# PROCESSOR_MEMORIES.net
KiCad netlist of a schematic drawn in Altium Designer
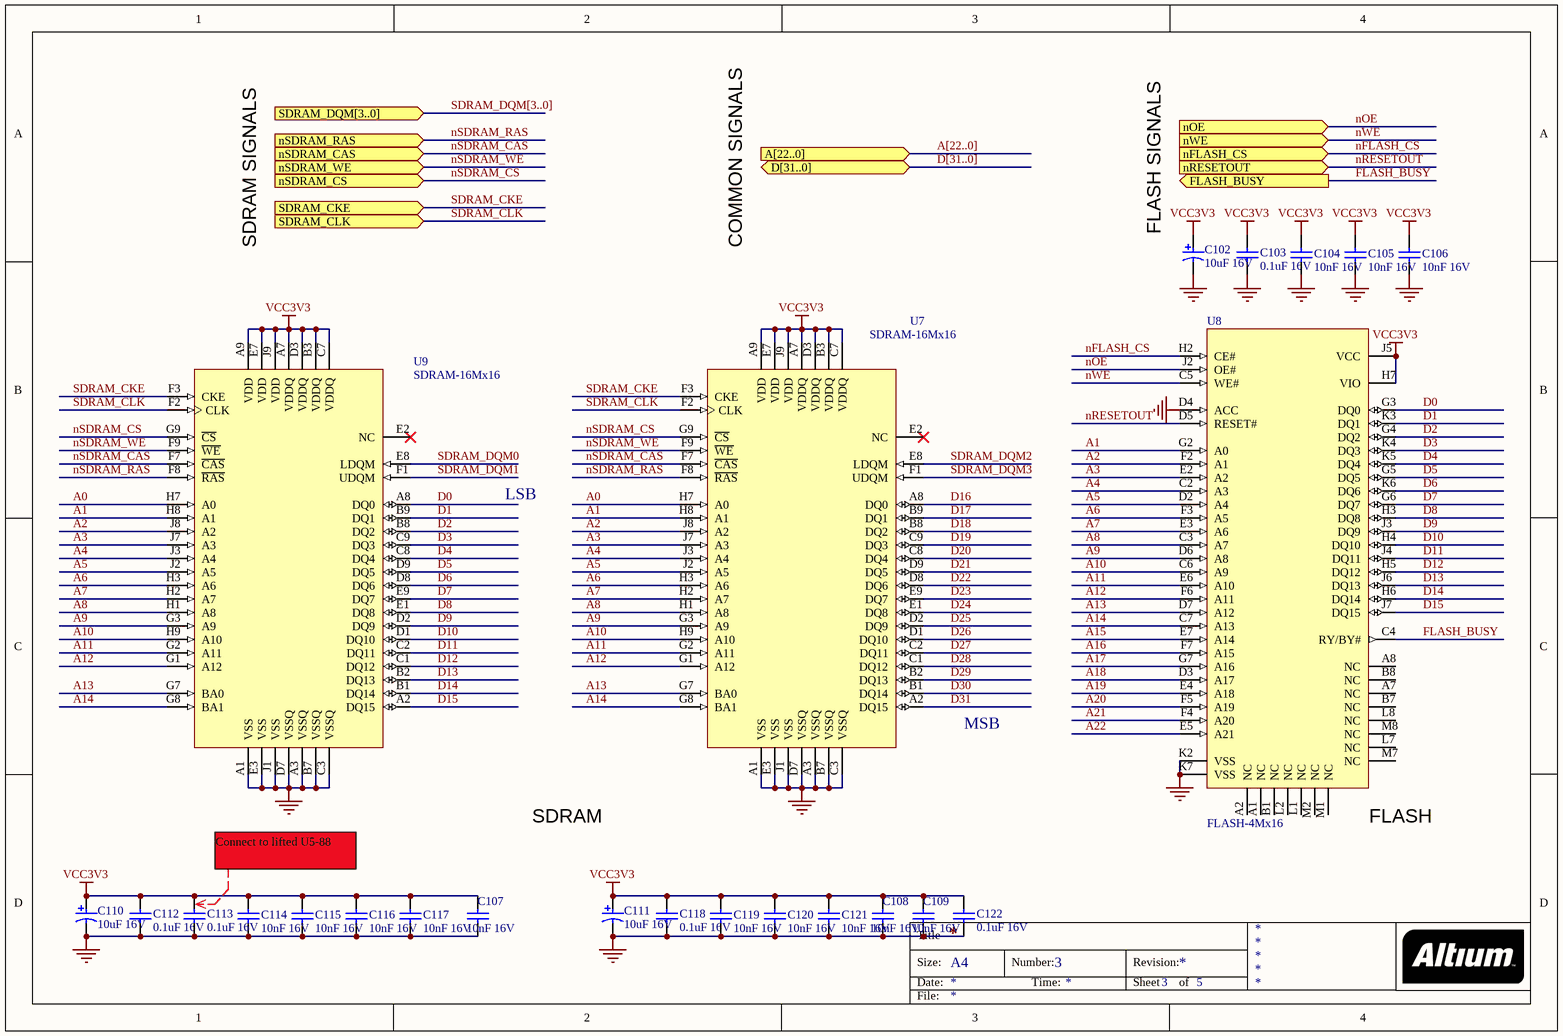
[diagram p0: PROCESSOR_MEMORIES.SCHDOC]

(export (version "E")
  (design (tool "Eeschema 10.0.6"))
  (components
    (comp (ref "C102")
      (value "10uF 16V")
      (footprint "CAPC3528")
      (description "Polar Capacitor")
      (libsource (lib "Altium Design Library") (part "CAP-P"))
    )
    (comp (ref "C103")
      (value "0.1uF 16V")
      (footprint "CAPC1005")
      (description "Capacitor")
      (libsource (lib "Altium Design Library") (part "CAP-NP"))
    )
    (comp (ref "C104")
      (value "10nF 16V")
      (footprint "CAPC1005")
      (description "Capacitor")
      (libsource (lib "Altium Design Library") (part "CAP-NP"))
    )
    (comp (ref "C105")
      (value "10nF 16V")
      (footprint "CAPC1005")
      (description "Capacitor")
      (libsource (lib "Altium Design Library") (part "CAP-NP"))
    )
    (comp (ref "C106")
      (value "10nF 16V")
      (footprint "CAPC1005")
      (description "Capacitor")
      (libsource (lib "Altium Design Library") (part "CAP-NP"))
    )
    (comp (ref "C107")
      (value "10nF 16V")
      (footprint "CAPC1005")
      (description "Capacitor")
      (libsource (lib "Altium Design Library") (part "CAP-NP"))
    )
    (comp (ref "C108")
      (value "10nF 16V")
      (footprint "CAPC1005")
      (description "Capacitor")
      (libsource (lib "Altium Design Library") (part "CAP-NP"))
    )
    (comp (ref "C109")
      (value "10nF 16V")
      (footprint "CAPC1005")
      (description "Capacitor")
      (libsource (lib "Altium Design Library") (part "CAP-NP"))
    )
    (comp (ref "C110")
      (value "10uF 16V")
      (footprint "CAPC3528")
      (description "Polar Capacitor")
      (libsource (lib "Altium Design Library") (part "CAP-P"))
    )
    (comp (ref "C111")
      (value "10uF 16V")
      (footprint "CAPC3528")
      (description "Polar Capacitor")
      (libsource (lib "Altium Design Library") (part "CAP-P"))
    )
    (comp (ref "C112")
      (value "0.1uF 16V")
      (footprint "CAPC1005")
      (description "Capacitor")
      (libsource (lib "Altium Design Library") (part "CAP-NP"))
    )
    (comp (ref "C113")
      (value "0.1uF 16V")
      (footprint "CAPC1005")
      (description "Capacitor")
      (libsource (lib "Altium Design Library") (part "CAP-NP"))
    )
    (comp (ref "C114")
      (value "10nF 16V")
      (footprint "CAPC1005")
      (description "Capacitor")
      (libsource (lib "Altium Design Library") (part "CAP-NP"))
    )
    (comp (ref "C115")
      (value "10nF 16V")
      (footprint "CAPC1005")
      (description "Capacitor")
      (libsource (lib "Altium Design Library") (part "CAP-NP"))
    )
    (comp (ref "C116")
      (value "10nF 16V")
      (footprint "CAPC1005")
      (description "Capacitor")
      (libsource (lib "Altium Design Library") (part "CAP-NP"))
    )
    (comp (ref "C117")
      (value "10nF 16V")
      (footprint "CAPC1005")
      (description "Capacitor")
      (libsource (lib "Altium Design Library") (part "CAP-NP"))
    )
    (comp (ref "C118")
      (value "0.1uF 16V")
      (footprint "CAPC1005")
      (description "Capacitor")
      (libsource (lib "Altium Design Library") (part "CAP-NP"))
    )
    (comp (ref "C119")
      (value "10nF 16V")
      (footprint "CAPC1005")
      (description "Capacitor")
      (libsource (lib "Altium Design Library") (part "CAP-NP"))
    )
    (comp (ref "C120")
      (value "10nF 16V")
      (footprint "CAPC1005")
      (description "Capacitor")
      (libsource (lib "Altium Design Library") (part "CAP-NP"))
    )
    (comp (ref "C121")
      (value "10nF 16V")
      (footprint "CAPC1005")
      (description "Capacitor")
      (libsource (lib "Altium Design Library") (part "CAP-NP"))
    )
    (comp (ref "C122")
      (value "0.1uF 16V")
      (footprint "CAPC1005")
      (description "Capacitor")
      (libsource (lib "Altium Design Library") (part "CAP-NP"))
    )
    (comp (ref "U7")
      (value "SDRAM-16Mx16")
      (footprint "BGA80P9X6-54")
      (description "256Mb Synchronous High-Speed CMOS DRAM, 16Mb x 16Bit x 4 Banks, 54-Ball FPGA, Commercial")
      (libsource (lib "Altium Design Library") (part "MT48LC16M16A2FG"))
    )
    (comp (ref "U8")
      (value "FLASH-4Mx16")
      (footprint "BGA80P12X8-63")
      (libsource (lib "Altium Design Library") (part "AM29LV640DU90RWHI"))
    )
    (comp (ref "U9")
      (value "SDRAM-16Mx16")
      (footprint "BGA80P9X6-54")
      (description "256Mb Synchronous High-Speed CMOS DRAM, 16Mb x 16Bit x 4 Banks, 54-Ball FPGA, Commercial")
      (libsource (lib "Altium Design Library") (part "MT48LC16M16A2FG"))
    )
  )
  (nets
    (net (code "1") (name "/A0") (class "Default")
      (node (ref "U7") (pin "H7") (pinfunction "A0_H7") (pintype "input"))
      (node (ref "U9") (pin "H7") (pinfunction "A0_H7") (pintype "input"))
    )
    (net (code "2") (name "/A1") (class "Default")
      (node (ref "U7") (pin "H8") (pinfunction "A1_H8") (pintype "input"))
      (node (ref "U8") (pin "G2") (pinfunction "A0_G2") (pintype "input"))
      (node (ref "U9") (pin "H8") (pinfunction "A1_H8") (pintype "input"))
    )
    (net (code "3") (name "/A2") (class "Default")
      (node (ref "U7") (pin "J8") (pinfunction "A2_J8") (pintype "input"))
      (node (ref "U8") (pin "F2") (pinfunction "A1_F2") (pintype "input"))
      (node (ref "U9") (pin "J8") (pinfunction "A2_J8") (pintype "input"))
    )
    (net (code "4") (name "/A3") (class "Default")
      (node (ref "U7") (pin "J7") (pinfunction "A3_J7") (pintype "input"))
      (node (ref "U8") (pin "E2") (pinfunction "A2_E2") (pintype "input"))
      (node (ref "U9") (pin "J7") (pinfunction "A3_J7") (pintype "input"))
    )
    (net (code "5") (name "/A4") (class "Default")
      (node (ref "U7") (pin "J3") (pinfunction "A4_J3") (pintype "input"))
      (node (ref "U8") (pin "C2") (pinfunction "A3_C2") (pintype "input"))
      (node (ref "U9") (pin "J3") (pinfunction "A4_J3") (pintype "input"))
    )
    (net (code "6") (name "/A5") (class "Default")
      (node (ref "U7") (pin "J2") (pinfunction "A5_J2") (pintype "input"))
      (node (ref "U8") (pin "D2") (pinfunction "A4_D2") (pintype "input"))
      (node (ref "U9") (pin "J2") (pinfunction "A5_J2") (pintype "input"))
    )
    (net (code "7") (name "/A6") (class "Default")
      (node (ref "U7") (pin "H3") (pinfunction "A6_H3") (pintype "input"))
      (node (ref "U8") (pin "F3") (pinfunction "A5_F3") (pintype "input"))
      (node (ref "U9") (pin "H3") (pinfunction "A6_H3") (pintype "input"))
    )
    (net (code "8") (name "/A7") (class "Default")
      (node (ref "U7") (pin "H2") (pinfunction "A7_H2") (pintype "input"))
      (node (ref "U8") (pin "E3") (pinfunction "A6_E3") (pintype "input"))
      (node (ref "U9") (pin "H2") (pinfunction "A7_H2") (pintype "input"))
    )
    (net (code "9") (name "/A8") (class "Default")
      (node (ref "U7") (pin "H1") (pinfunction "A8_H1") (pintype "input"))
      (node (ref "U8") (pin "C3") (pinfunction "A7_C3") (pintype "input"))
      (node (ref "U9") (pin "H1") (pinfunction "A8_H1") (pintype "input"))
    )
    (net (code "10") (name "/A9") (class "Default")
      (node (ref "U7") (pin "G3") (pinfunction "A9_G3") (pintype "input"))
      (node (ref "U8") (pin "D6") (pinfunction "A8_D6") (pintype "input"))
      (node (ref "U9") (pin "G3") (pinfunction "A9_G3") (pintype "input"))
    )
    (net (code "11") (name "/A10") (class "Default")
      (node (ref "U7") (pin "H9") (pinfunction "A10_H9") (pintype "input"))
      (node (ref "U8") (pin "C6") (pinfunction "A9_C6") (pintype "input"))
      (node (ref "U9") (pin "H9") (pinfunction "A10_H9") (pintype "input"))
    )
    (net (code "12") (name "/A11") (class "Default")
      (node (ref "U7") (pin "G2") (pinfunction "A11_G2") (pintype "input"))
      (node (ref "U8") (pin "E6") (pinfunction "A10_E6") (pintype "input"))
      (node (ref "U9") (pin "G2") (pinfunction "A11_G2") (pintype "input"))
    )
    (net (code "13") (name "/A12") (class "Default")
      (node (ref "U7") (pin "G1") (pinfunction "A12_G1") (pintype "input"))
      (node (ref "U8") (pin "F6") (pinfunction "A11_F6") (pintype "input"))
      (node (ref "U9") (pin "G1") (pinfunction "A12_G1") (pintype "input"))
    )
    (net (code "14") (name "/A13") (class "Default")
      (node (ref "U7") (pin "G7") (pinfunction "BA0_G7") (pintype "input"))
      (node (ref "U8") (pin "D7") (pinfunction "A12_D7") (pintype "input"))
      (node (ref "U9") (pin "G7") (pinfunction "BA0_G7") (pintype "input"))
    )
    (net (code "15") (name "/A14") (class "Default")
      (node (ref "U7") (pin "G8") (pinfunction "BA1_G8") (pintype "input"))
      (node (ref "U8") (pin "C7") (pinfunction "A13_C7") (pintype "input"))
      (node (ref "U9") (pin "G8") (pinfunction "BA1_G8") (pintype "input"))
    )
    (net (code "16") (name "/A15") (class "Default")
      (node (ref "U8") (pin "E7") (pinfunction "A14_E7") (pintype "input"))
    )
    (net (code "17") (name "/A16") (class "Default")
      (node (ref "U8") (pin "F7") (pinfunction "A15_F7") (pintype "input"))
    )
    (net (code "18") (name "/A17") (class "Default")
      (node (ref "U8") (pin "G7") (pinfunction "A16_G7") (pintype "input"))
    )
    (net (code "19") (name "/A18") (class "Default")
      (node (ref "U8") (pin "D3") (pinfunction "A17_D3") (pintype "input"))
    )
    (net (code "20") (name "/A19") (class "Default")
      (node (ref "U8") (pin "E4") (pinfunction "A18_E4") (pintype "input"))
    )
    (net (code "21") (name "/A20") (class "Default")
      (node (ref "U8") (pin "F5") (pinfunction "A19_F5") (pintype "input"))
    )
    (net (code "22") (name "/A21") (class "Default")
      (node (ref "U8") (pin "F4") (pinfunction "A20_F4") (pintype "input"))
    )
    (net (code "23") (name "/A22") (class "Default")
      (node (ref "U8") (pin "E5") (pinfunction "A21_E5") (pintype "input"))
    )
    (net (code "25") (name "/D0") (class "Default")
      (node (ref "U8") (pin "G3") (pinfunction "DQ0_G3") (pintype "bidirectional"))
      (node (ref "U9") (pin "A8") (pinfunction "DQ0_A8") (pintype "bidirectional"))
    )
    (net (code "26") (name "/D1") (class "Default")
      (node (ref "U8") (pin "K3") (pinfunction "DQ1_K3") (pintype "bidirectional"))
      (node (ref "U9") (pin "B9") (pinfunction "DQ1_B9") (pintype "bidirectional"))
    )
    (net (code "27") (name "/D2") (class "Default")
      (node (ref "U8") (pin "G4") (pinfunction "DQ2_G4") (pintype "bidirectional"))
      (node (ref "U9") (pin "B8") (pinfunction "DQ2_B8") (pintype "bidirectional"))
    )
    (net (code "28") (name "/D3") (class "Default")
      (node (ref "U8") (pin "K4") (pinfunction "DQ3_K4") (pintype "bidirectional"))
      (node (ref "U9") (pin "C9") (pinfunction "DQ3_C9") (pintype "bidirectional"))
    )
    (net (code "29") (name "/D4") (class "Default")
      (node (ref "U8") (pin "K5") (pinfunction "DQ4_K5") (pintype "bidirectional"))
      (node (ref "U9") (pin "C8") (pinfunction "DQ4_C8") (pintype "bidirectional"))
    )
    (net (code "30") (name "/D5") (class "Default")
      (node (ref "U8") (pin "G5") (pinfunction "DQ5_G5") (pintype "bidirectional"))
      (node (ref "U9") (pin "D9") (pinfunction "DQ5_D9") (pintype "bidirectional"))
    )
    (net (code "31") (name "/D6") (class "Default")
      (node (ref "U8") (pin "K6") (pinfunction "DQ6_K6") (pintype "bidirectional"))
      (node (ref "U9") (pin "D8") (pinfunction "DQ6_D8") (pintype "bidirectional"))
    )
    (net (code "32") (name "/D7") (class "Default")
      (node (ref "U8") (pin "G6") (pinfunction "DQ7_G6") (pintype "bidirectional"))
      (node (ref "U9") (pin "E9") (pinfunction "DQ7_E9") (pintype "bidirectional"))
    )
    (net (code "33") (name "/D8") (class "Default")
      (node (ref "U8") (pin "H3") (pinfunction "DQ8_H3") (pintype "bidirectional"))
      (node (ref "U9") (pin "E1") (pinfunction "DQ8_E1") (pintype "bidirectional"))
    )
    (net (code "34") (name "/D9") (class "Default")
      (node (ref "U8") (pin "J3") (pinfunction "DQ9_J3") (pintype "bidirectional"))
      (node (ref "U9") (pin "D2") (pinfunction "DQ9_D2") (pintype "bidirectional"))
    )
    (net (code "35") (name "/D10") (class "Default")
      (node (ref "U8") (pin "H4") (pinfunction "DQ10_H4") (pintype "bidirectional"))
      (node (ref "U9") (pin "D1") (pinfunction "DQ10_D1") (pintype "bidirectional"))
    )
    (net (code "36") (name "/D11") (class "Default")
      (node (ref "U8") (pin "J4") (pinfunction "DQ11_J4") (pintype "bidirectional"))
      (node (ref "U9") (pin "C2") (pinfunction "DQ11_C2") (pintype "bidirectional"))
    )
    (net (code "37") (name "/D12") (class "Default")
      (node (ref "U8") (pin "H5") (pinfunction "DQ12_H5") (pintype "bidirectional"))
      (node (ref "U9") (pin "C1") (pinfunction "DQ12_C1") (pintype "bidirectional"))
    )
    (net (code "38") (name "/D13") (class "Default")
      (node (ref "U8") (pin "J6") (pinfunction "DQ13_J6") (pintype "bidirectional"))
      (node (ref "U9") (pin "B2") (pinfunction "DQ13_B2") (pintype "bidirectional"))
    )
    (net (code "39") (name "/D14") (class "Default")
      (node (ref "U8") (pin "H6") (pinfunction "DQ14_H6") (pintype "bidirectional"))
      (node (ref "U9") (pin "B1") (pinfunction "DQ14_B1") (pintype "bidirectional"))
    )
    (net (code "40") (name "/D15") (class "Default")
      (node (ref "U8") (pin "J7") (pinfunction "DQ15_J7") (pintype "bidirectional"))
      (node (ref "U9") (pin "A2") (pinfunction "DQ15_A2") (pintype "bidirectional"))
    )
    (net (code "41") (name "/D16") (class "Default")
      (node (ref "U7") (pin "A8") (pinfunction "DQ0_A8") (pintype "bidirectional"))
    )
    (net (code "42") (name "/D17") (class "Default")
      (node (ref "U7") (pin "B9") (pinfunction "DQ1_B9") (pintype "bidirectional"))
    )
    (net (code "43") (name "/D18") (class "Default")
      (node (ref "U7") (pin "B8") (pinfunction "DQ2_B8") (pintype "bidirectional"))
    )
    (net (code "44") (name "/D19") (class "Default")
      (node (ref "U7") (pin "C9") (pinfunction "DQ3_C9") (pintype "bidirectional"))
    )
    (net (code "45") (name "/D20") (class "Default")
      (node (ref "U7") (pin "C8") (pinfunction "DQ4_C8") (pintype "bidirectional"))
    )
    (net (code "46") (name "/D21") (class "Default")
      (node (ref "U7") (pin "D9") (pinfunction "DQ5_D9") (pintype "bidirectional"))
    )
    (net (code "47") (name "/D22") (class "Default")
      (node (ref "U7") (pin "D8") (pinfunction "DQ6_D8") (pintype "bidirectional"))
    )
    (net (code "48") (name "/D23") (class "Default")
      (node (ref "U7") (pin "E9") (pinfunction "DQ7_E9") (pintype "bidirectional"))
    )
    (net (code "49") (name "/D24") (class "Default")
      (node (ref "U7") (pin "E1") (pinfunction "DQ8_E1") (pintype "bidirectional"))
    )
    (net (code "50") (name "/D25") (class "Default")
      (node (ref "U7") (pin "D2") (pinfunction "DQ9_D2") (pintype "bidirectional"))
    )
    (net (code "51") (name "/D26") (class "Default")
      (node (ref "U7") (pin "D1") (pinfunction "DQ10_D1") (pintype "bidirectional"))
    )
    (net (code "52") (name "/D27") (class "Default")
      (node (ref "U7") (pin "C2") (pinfunction "DQ11_C2") (pintype "bidirectional"))
    )
    (net (code "53") (name "/D28") (class "Default")
      (node (ref "U7") (pin "C1") (pinfunction "DQ12_C1") (pintype "bidirectional"))
    )
    (net (code "54") (name "/D29") (class "Default")
      (node (ref "U7") (pin "B2") (pinfunction "DQ13_B2") (pintype "bidirectional"))
    )
    (net (code "55") (name "/D30") (class "Default")
      (node (ref "U7") (pin "B1") (pinfunction "DQ14_B1") (pintype "bidirectional"))
    )
    (net (code "56") (name "/D31") (class "Default")
      (node (ref "U7") (pin "A2") (pinfunction "DQ15_A2") (pintype "bidirectional"))
    )
    (net (code "58") (name "/FLASH_BUSY") (class "Default")
      (node (ref "U8") (pin "C4") (pinfunction "RY/BY#_C4") (pintype "output"))
    )
    (net (code "59") (name "/SDRAM_CKE") (class "Default")
      (node (ref "U7") (pin "F3") (pinfunction "CKE_F3") (pintype "input"))
      (node (ref "U9") (pin "F3") (pinfunction "CKE_F3") (pintype "input"))
    )
    (net (code "60") (name "/SDRAM_CLK") (class "Default")
      (node (ref "U7") (pin "F2") (pinfunction "CLK_F2") (pintype "input"))
      (node (ref "U9") (pin "F2") (pinfunction "CLK_F2") (pintype "input"))
    )
    (net (code "61") (name "/SDRAM_DQM0") (class "Default")
      (node (ref "U9") (pin "E8") (pinfunction "LDQM_E8") (pintype "input"))
    )
    (net (code "62") (name "/SDRAM_DQM1") (class "Default")
      (node (ref "U9") (pin "F1") (pinfunction "UDQM_F1") (pintype "input"))
    )
    (net (code "63") (name "/SDRAM_DQM2") (class "Default")
      (node (ref "U7") (pin "E8") (pinfunction "LDQM_E8") (pintype "input"))
    )
    (net (code "64") (name "/SDRAM_DQM3") (class "Default")
      (node (ref "U7") (pin "F1") (pinfunction "UDQM_F1") (pintype "input"))
    )
    (net (code "66") (name "/nFLASH_CS") (class "Default")
      (node (ref "U8") (pin "H2") (pinfunction "CE#_H2") (pintype "input"))
    )
    (net (code "67") (name "/nOE") (class "Default")
      (node (ref "U8") (pin "J2") (pinfunction "OE#_J2") (pintype "input"))
    )
    (net (code "68") (name "/nRESETOUT") (class "Default")
      (node (ref "U8") (pin "D5") (pinfunction "RESET#_D5") (pintype "input"))
    )
    (net (code "69") (name "/nSDRAM_CAS") (class "Default")
      (node (ref "U7") (pin "F7") (pinfunction "~{CAS}_F7") (pintype "input"))
      (node (ref "U9") (pin "F7") (pinfunction "~{CAS}_F7") (pintype "input"))
    )
    (net (code "70") (name "/nSDRAM_CS") (class "Default")
      (node (ref "U7") (pin "G9") (pinfunction "~{CS}_G9") (pintype "input"))
      (node (ref "U9") (pin "G9") (pinfunction "~{CS}_G9") (pintype "input"))
    )
    (net (code "71") (name "/nSDRAM_RAS") (class "Default")
      (node (ref "U7") (pin "F8") (pinfunction "~{RAS}_F8") (pintype "input"))
      (node (ref "U9") (pin "F8") (pinfunction "~{RAS}_F8") (pintype "input"))
    )
    (net (code "72") (name "/nSDRAM_WE") (class "Default")
      (node (ref "U7") (pin "F9") (pinfunction "~{WE}_F9") (pintype "input"))
      (node (ref "U9") (pin "F9") (pinfunction "~{WE}_F9") (pintype "input"))
    )
    (net (code "73") (name "/nWE") (class "Default")
      (node (ref "U8") (pin "C5") (pinfunction "WE#_C5") (pintype "input"))
    )
    (net (code "74") (name "GND") (class "Default")
      (node (ref "C102") (pin "2") (pinfunction "2_2") (pintype "passive"))
      (node (ref "C103") (pin "2") (pinfunction "2_2") (pintype "passive"))
      (node (ref "C104") (pin "2") (pinfunction "2_2") (pintype "passive"))
      (node (ref "C105") (pin "2") (pinfunction "2_2") (pintype "passive"))
      (node (ref "C106") (pin "2") (pinfunction "2_2") (pintype "passive"))
      (node (ref "C107") (pin "2") (pinfunction "2_2") (pintype "passive"))
      (node (ref "C108") (pin "2") (pinfunction "2_2") (pintype "passive"))
      (node (ref "C109") (pin "2") (pinfunction "2_2") (pintype "passive"))
      (node (ref "C110") (pin "2") (pinfunction "2_2") (pintype "passive"))
      (node (ref "C111") (pin "2") (pinfunction "2_2") (pintype "passive"))
      (node (ref "C112") (pin "2") (pinfunction "2_2") (pintype "passive"))
      (node (ref "C113") (pin "2") (pinfunction "2_2") (pintype "passive"))
      (node (ref "C114") (pin "2") (pinfunction "2_2") (pintype "passive"))
      (node (ref "C115") (pin "2") (pinfunction "2_2") (pintype "passive"))
      (node (ref "C116") (pin "2") (pinfunction "2_2") (pintype "passive"))
      (node (ref "C117") (pin "2") (pinfunction "2_2") (pintype "passive"))
      (node (ref "C118") (pin "2") (pinfunction "2_2") (pintype "passive"))
      (node (ref "C119") (pin "2") (pinfunction "2_2") (pintype "passive"))
      (node (ref "C120") (pin "2") (pinfunction "2_2") (pintype "passive"))
      (node (ref "C121") (pin "2") (pinfunction "2_2") (pintype "passive"))
      (node (ref "C122") (pin "2") (pinfunction "2_2") (pintype "passive"))
      (node (ref "U7") (pin "A1") (pinfunction "VSS_A1") (pintype "power_in"))
      (node (ref "U7") (pin "A3") (pinfunction "VSSQ_A3") (pintype "power_in"))
      (node (ref "U7") (pin "B7") (pinfunction "VSSQ_B7") (pintype "power_in"))
      (node (ref "U7") (pin "C3") (pinfunction "VSSQ_C3") (pintype "power_in"))
      (node (ref "U7") (pin "D7") (pinfunction "VSSQ_D7") (pintype "power_in"))
      (node (ref "U7") (pin "E3") (pinfunction "VSS_E3") (pintype "power_in"))
      (node (ref "U7") (pin "J1") (pinfunction "VSS_J1") (pintype "power_in"))
      (node (ref "U8") (pin "D4") (pinfunction "ACC_D4") (pintype "input"))
      (node (ref "U8") (pin "K2") (pinfunction "VSS_K2") (pintype "power_in"))
      (node (ref "U8") (pin "K7") (pinfunction "VSS_K7") (pintype "power_in"))
      (node (ref "U9") (pin "A1") (pinfunction "VSS_A1") (pintype "power_in"))
      (node (ref "U9") (pin "A3") (pinfunction "VSSQ_A3") (pintype "power_in"))
      (node (ref "U9") (pin "B7") (pinfunction "VSSQ_B7") (pintype "power_in"))
      (node (ref "U9") (pin "C3") (pinfunction "VSSQ_C3") (pintype "power_in"))
      (node (ref "U9") (pin "D7") (pinfunction "VSSQ_D7") (pintype "power_in"))
      (node (ref "U9") (pin "E3") (pinfunction "VSS_E3") (pintype "power_in"))
      (node (ref "U9") (pin "J1") (pinfunction "VSS_J1") (pintype "power_in"))
    )
    (net (code "75") (name "VCC3V3") (class "Default")
      (node (ref "C102") (pin "1") (pinfunction "1_1") (pintype "passive"))
      (node (ref "C103") (pin "1") (pinfunction "1_1") (pintype "passive"))
      (node (ref "C104") (pin "1") (pinfunction "1_1") (pintype "passive"))
      (node (ref "C105") (pin "1") (pinfunction "1_1") (pintype "passive"))
      (node (ref "C106") (pin "1") (pinfunction "1_1") (pintype "passive"))
      (node (ref "C107") (pin "1") (pinfunction "1_1") (pintype "passive"))
      (node (ref "C108") (pin "1") (pinfunction "1_1") (pintype "passive"))
      (node (ref "C109") (pin "1") (pinfunction "1_1") (pintype "passive"))
      (node (ref "C110") (pin "1") (pinfunction "1_1") (pintype "passive"))
      (node (ref "C111") (pin "1") (pinfunction "1_1") (pintype "passive"))
      (node (ref "C112") (pin "1") (pinfunction "1_1") (pintype "passive"))
      (node (ref "C113") (pin "1") (pinfunction "1_1") (pintype "passive"))
      (node (ref "C114") (pin "1") (pinfunction "1_1") (pintype "passive"))
      (node (ref "C115") (pin "1") (pinfunction "1_1") (pintype "passive"))
      (node (ref "C116") (pin "1") (pinfunction "1_1") (pintype "passive"))
      (node (ref "C117") (pin "1") (pinfunction "1_1") (pintype "passive"))
      (node (ref "C118") (pin "1") (pinfunction "1_1") (pintype "passive"))
      (node (ref "C119") (pin "1") (pinfunction "1_1") (pintype "passive"))
      (node (ref "C120") (pin "1") (pinfunction "1_1") (pintype "passive"))
      (node (ref "C121") (pin "1") (pinfunction "1_1") (pintype "passive"))
      (node (ref "C122") (pin "1") (pinfunction "1_1") (pintype "passive"))
      (node (ref "U7") (pin "A7") (pinfunction "VDDQ_A7") (pintype "power_in"))
      (node (ref "U7") (pin "A9") (pinfunction "VDD_A9") (pintype "power_in"))
      (node (ref "U7") (pin "B3") (pinfunction "VDDQ_B3") (pintype "power_in"))
      (node (ref "U7") (pin "C7") (pinfunction "VDDQ_C7") (pintype "power_in"))
      (node (ref "U7") (pin "D3") (pinfunction "VDDQ_D3") (pintype "power_in"))
      (node (ref "U7") (pin "E7") (pinfunction "VDD_E7") (pintype "power_in"))
      (node (ref "U7") (pin "J9") (pinfunction "VDD_J9") (pintype "power_in"))
      (node (ref "U8") (pin "H7") (pinfunction "VIO_H7") (pintype "power_in"))
      (node (ref "U8") (pin "J5") (pinfunction "VCC_J5") (pintype "power_in"))
      (node (ref "U9") (pin "A7") (pinfunction "VDDQ_A7") (pintype "power_in"))
      (node (ref "U9") (pin "A9") (pinfunction "VDD_A9") (pintype "power_in"))
      (node (ref "U9") (pin "B3") (pinfunction "VDDQ_B3") (pintype "power_in"))
      (node (ref "U9") (pin "C7") (pinfunction "VDDQ_C7") (pintype "power_in"))
      (node (ref "U9") (pin "D3") (pinfunction "VDDQ_D3") (pintype "power_in"))
      (node (ref "U9") (pin "E7") (pinfunction "VDD_E7") (pintype "power_in"))
      (node (ref "U9") (pin "J9") (pinfunction "VDD_J9") (pintype "power_in"))
    )
    (net (code "76") (name "unconnected-(U7-NC-PadE2)") (class "Default")
      (node (ref "U7") (pin "E2") (pinfunction "NC_E2") (pintype "passive+no_connect"))
    )
    (net (code "77") (name "unconnected-(U8-NC-PadA1)") (class "Default")
      (node (ref "U8") (pin "A1") (pinfunction "NC_A1") (pintype "passive"))
    )
    (net (code "78") (name "unconnected-(U8-NC-PadA2)") (class "Default")
      (node (ref "U8") (pin "A2") (pinfunction "NC_A2") (pintype "passive"))
    )
    (net (code "79") (name "unconnected-(U8-NC-PadA7)") (class "Default")
      (node (ref "U8") (pin "A7") (pinfunction "NC_A7") (pintype "passive"))
    )
    (net (code "80") (name "unconnected-(U8-NC-PadA8)") (class "Default")
      (node (ref "U8") (pin "A8") (pinfunction "NC_A8") (pintype "passive"))
    )
    (net (code "81") (name "unconnected-(U8-NC-PadB1)") (class "Default")
      (node (ref "U8") (pin "B1") (pinfunction "NC_B1") (pintype "passive"))
    )
    (net (code "82") (name "unconnected-(U8-NC-PadB7)") (class "Default")
      (node (ref "U8") (pin "B7") (pinfunction "NC_B7") (pintype "passive"))
    )
    (net (code "83") (name "unconnected-(U8-NC-PadB8)") (class "Default")
      (node (ref "U8") (pin "B8") (pinfunction "NC_B8") (pintype "passive"))
    )
    (net (code "84") (name "unconnected-(U8-NC-PadL1)") (class "Default")
      (node (ref "U8") (pin "L1") (pinfunction "NC_L1") (pintype "passive"))
    )
    (net (code "85") (name "unconnected-(U8-NC-PadL2)") (class "Default")
      (node (ref "U8") (pin "L2") (pinfunction "NC_L2") (pintype "passive"))
    )
    (net (code "86") (name "unconnected-(U8-NC-PadL7)") (class "Default")
      (node (ref "U8") (pin "L7") (pinfunction "NC_L7") (pintype "passive"))
    )
    (net (code "87") (name "unconnected-(U8-NC-PadL8)") (class "Default")
      (node (ref "U8") (pin "L8") (pinfunction "NC_L8") (pintype "passive"))
    )
    (net (code "88") (name "unconnected-(U8-NC-PadM1)") (class "Default")
      (node (ref "U8") (pin "M1") (pinfunction "NC_M1") (pintype "passive"))
    )
    (net (code "89") (name "unconnected-(U8-NC-PadM2)") (class "Default")
      (node (ref "U8") (pin "M2") (pinfunction "NC_M2") (pintype "passive"))
    )
    (net (code "90") (name "unconnected-(U8-NC-PadM7)") (class "Default")
      (node (ref "U8") (pin "M7") (pinfunction "NC_M7") (pintype "passive"))
    )
    (net (code "91") (name "unconnected-(U8-NC-PadM8)") (class "Default")
      (node (ref "U8") (pin "M8") (pinfunction "NC_M8") (pintype "passive"))
    )
    (net (code "92") (name "unconnected-(U9-NC-PadE2)") (class "Default")
      (node (ref "U9") (pin "E2") (pinfunction "NC_E2") (pintype "passive+no_connect"))
    )
  )
)
